# StabImp.net
KiCad netlist of a schematic drawn in Altium Designer
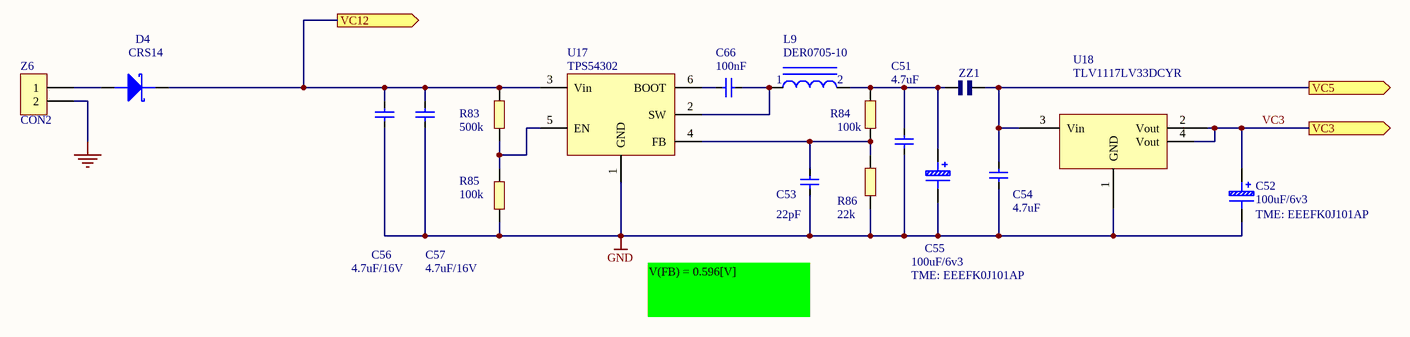
[diagram p0: StabImp.SchDoc]

(export (version "E")
  (design (tool "Eeschema 10.0.6"))
  (components
    (comp (ref "C51") (value "4.7uF") (footprint "0805C") (libsource (lib "*") (part "CAP")))
    (comp (ref "C52")
      (value "100uF/6v3")
      (footprint "CAP_SMD_ELEK_D")
      (description "EEEFK0J101AP")
      (fields (field (name "TME") "EEEFK0J101AP"))
      (libsource (lib "GkSchlib") (part "CapTantal"))
    )
    (comp (ref "C53") (value "22pF") (footprint "0603C") (libsource (lib "*") (part "CAP")))
    (comp (ref "C54") (value "4.7uF") (footprint "0805C") (libsource (lib "*") (part "CAP")))
    (comp (ref "C55")
      (value "100uF/6v3")
      (footprint "CAP_SMD_ELEK_D")
      (description "EEEFK0J101AP")
      (fields (field (name "TME") "EEEFK0J101AP"))
      (libsource (lib "GkSchlib") (part "CapTantal"))
    )
    (comp (ref "C56") (value "4.7uF/16V") (footprint "0805C") (libsource (lib "*") (part "CAP")))
    (comp (ref "C57") (value "4.7uF/16V") (footprint "0805C") (libsource (lib "*") (part "CAP")))
    (comp (ref "C66") (value "100nF") (footprint "0603C") (libsource (lib "*") (part "CAP")))
    (comp (ref "D4")
      (value "CRS14")
      (footprint "1206D")
      (description "Schottky Diode")
      (libsource (lib "*") (part "DIODE SCHOTTKY"))
    )
    (comp (ref "L9") (value "DER0705-10") (footprint "DER0705_1") (libsource (lib "*") (part "CEWKA_1")))
    (comp (ref "R83") (value "500k") (footprint "0603R") (libsource (lib "*") (part "RES3")))
    (comp (ref "R84") (value "100k") (footprint "0603R") (libsource (lib "*") (part "RES3")))
    (comp (ref "R85") (value "100k") (footprint "0603R") (libsource (lib "*") (part "RES3")))
    (comp (ref "R86") (value "22k") (footprint "0603R") (libsource (lib "*") (part "RES3")))
    (comp (ref "U17")
      (value "TPS54302")
      (footprint "SOT-23-1.1")
      (libsource (lib "GkSchlib") (part "TPS54302"))
    )
    (comp (ref "U18") (value "TLV1117LV33DCYR") (footprint "SOT223") (libsource (lib "*") (part "LD1117V33")))
    (comp (ref "Z6")
      (value "CON2")
      (footprint "ARC-2-5.08")
      (description "Connector")
      (libsource (lib "*") (part "CON2"))
    )
    (comp (ref "ZZ1") (value "ZWORA") (footprint "ZW3") (libsource (lib "ElhosSchLib") (part "ZWORA")))
  )
  (nets
    (net (code "1") (name "/VC3") (class "Default")
      (node (ref "C52") (pin "2") (pintype "passive"))
      (node (ref "U18") (pin "2") (pinfunction "Vout_2") (pintype "passive"))
      (node (ref "U18") (pin "4") (pinfunction "Vout_4") (pintype "passive"))
    )
    (net (code "2") (name "/VC5") (class "Default")
      (node (ref "C54") (pin "2") (pintype "passive"))
      (node (ref "U18") (pin "3") (pinfunction "Vin_3") (pintype "passive"))
      (node (ref "ZZ1") (pin "2") (pintype "passive"))
    )
    (net (code "3") (name "/VC12") (class "Default")
      (node (ref "C56") (pin "2") (pintype "passive"))
      (node (ref "C57") (pin "2") (pintype "passive"))
      (node (ref "D4") (pin "K") (pinfunction "K_K") (pintype "passive"))
      (node (ref "R83") (pin "1") (pintype "passive"))
      (node (ref "U17") (pin "3") (pinfunction "Vin_3") (pintype "passive"))
    )
    (net (code "4") (name "GND") (class "Default")
      (node (ref "C51") (pin "1") (pintype "passive"))
      (node (ref "C52") (pin "1") (pintype "passive"))
      (node (ref "C53") (pin "1") (pintype "passive"))
      (node (ref "C54") (pin "1") (pintype "passive"))
      (node (ref "C55") (pin "1") (pintype "passive"))
      (node (ref "C56") (pin "1") (pintype "passive"))
      (node (ref "C57") (pin "1") (pintype "passive"))
      (node (ref "R85") (pin "2") (pintype "passive"))
      (node (ref "R86") (pin "2") (pintype "passive"))
      (node (ref "U17") (pin "1") (pinfunction "GND_1") (pintype "passive"))
      (node (ref "U18") (pin "1") (pinfunction "GND_1") (pintype "passive"))
      (node (ref "Z6") (pin "2") (pinfunction "2_2") (pintype "passive"))
    )
    (net (code "5") (name "Net-(C51-Pad2)") (class "Default")
      (node (ref "C51") (pin "2") (pintype "passive"))
      (node (ref "C55") (pin "2") (pintype "passive"))
      (node (ref "L9") (pin "2") (pintype "passive"))
      (node (ref "R84") (pin "1") (pintype "passive"))
      (node (ref "ZZ1") (pin "1") (pintype "passive"))
    )
    (net (code "6") (name "Net-(D4-PadA)") (class "Default")
      (node (ref "D4") (pin "A") (pinfunction "A_A") (pintype "passive"))
      (node (ref "Z6") (pin "1") (pinfunction "1_1") (pintype "passive"))
    )
    (net (code "7") (name "Net-(U17-BOOT)") (class "Default")
      (node (ref "C66") (pin "2") (pintype "passive"))
      (node (ref "U17") (pin "6") (pinfunction "BOOT_6") (pintype "passive"))
    )
    (net (code "8") (name "Net-(U17-EN)") (class "Default")
      (node (ref "R83") (pin "2") (pintype "passive"))
      (node (ref "R85") (pin "1") (pintype "passive"))
      (node (ref "U17") (pin "5") (pinfunction "EN_5") (pintype "passive"))
    )
    (net (code "9") (name "Net-(U17-FB)") (class "Default")
      (node (ref "C53") (pin "2") (pintype "passive"))
      (node (ref "R84") (pin "2") (pintype "passive"))
      (node (ref "R86") (pin "1") (pintype "passive"))
      (node (ref "U17") (pin "4") (pinfunction "FB_4") (pintype "passive"))
    )
    (net (code "10") (name "Net-(U17-SW)") (class "Default")
      (node (ref "C66") (pin "1") (pintype "passive"))
      (node (ref "L9") (pin "1") (pintype "passive"))
      (node (ref "U17") (pin "2") (pinfunction "SW_2") (pintype "passive"))
    )
  )
)
